# PowerSystem.net
KiCad netlist of a schematic drawn in Altium Designer
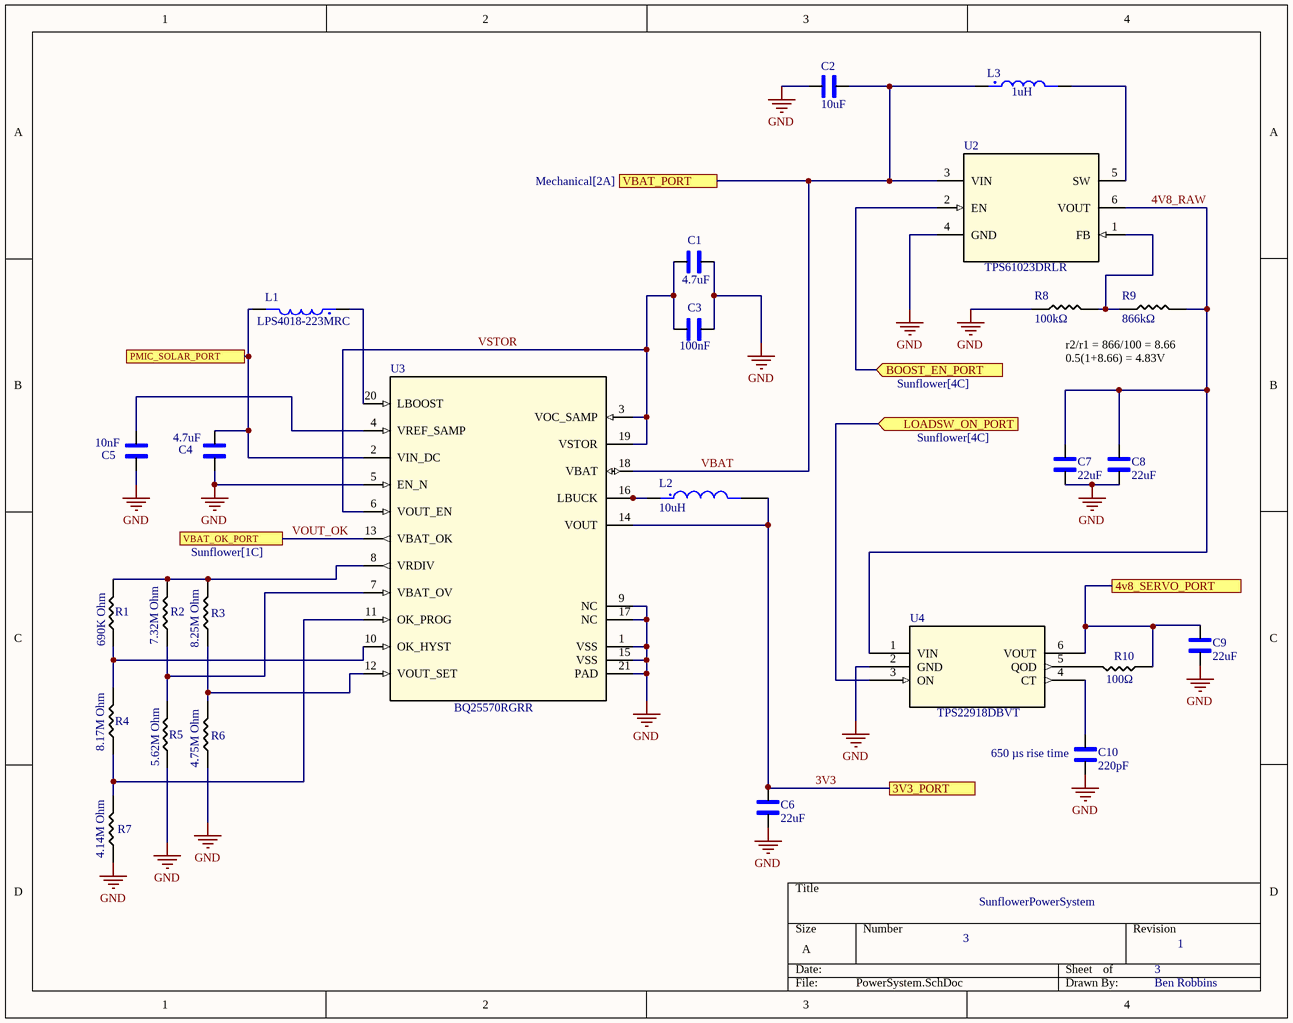
[diagram p0: PowerSystem.SchDoc]

(export (version "E")
  (design (tool "Eeschema 10.0.6"))
  (components
    (comp (ref "C1")
      (value "4.7uF")
      (footprint "0805_Capacitor")
      (description "4.7 µF ceramic input capacitor")
      (libsource (lib "SunflowerSCH") (part "C_0805_4u7"))
    )
    (comp (ref "C2")
      (value "10uF")
      (footprint "0805_Capacitor")
      (description "10 µF ceramic input capacitor")
      (libsource (lib "SunflowerSCH") (part "C_0805_10uF"))
    )
    (comp (ref "C3")
      (value "100nF")
      (footprint "0402_Capacitor")
      (description "0402 ceramic decoupling capacitor, 0.1 µF")
      (fields (field (name "MFR PART #") "CL05A105KA5NQNC") (field (name "LCSC PART#") "C52923"))
      (libsource (lib "SunflowerSCH") (part "C_0402_100nF"))
    )
    (comp (ref "C4")
      (value "4.7uF")
      (footprint "0805_Capacitor")
      (description "4.7 µF ceramic input capacitor")
      (libsource (lib "SunflowerSCH") (part "C_0805_4u7"))
    )
    (comp (ref "C5")
      (value "10nF")
      (footprint "0402_Capacitor")
      (description "10 nF low-leakage MPPT reference capacitor")
      (fields (field (name "MFR PART #") "CL05A105KA5NQNC") (field (name "LCSC PART#") "C52923"))
      (libsource (lib "SunflowerSCH") (part "C_0402_10nF"))
    )
    (comp (ref "C6")
      (value "22uF")
      (footprint "0805_Capacitor")
      (description "22 µF ceramic buck converter output capacitor")
      (libsource (lib "SunflowerSCH") (part "C_0805_22uF"))
    )
    (comp (ref "C7")
      (value "22uF")
      (footprint "0805_Capacitor")
      (description "22 µF ceramic buck converter output capacitor")
      (fields (field (name "DIGIKEY PART NUMBER") "1276-7092-1-ND"))
      (libsource (lib "SunflowerSCH") (part "C_0805_22uF"))
    )
    (comp (ref "C8")
      (value "22uF")
      (footprint "0805_Capacitor")
      (description "22 µF ceramic buck converter output capacitor")
      (fields (field (name "DIGIKEY PART NUMBER") "1276-7092-1-ND"))
      (libsource (lib "SunflowerSCH") (part "C_0805_22uF"))
    )
    (comp (ref "C9")
      (value "22uF")
      (footprint "0805_Capacitor")
      (description "22 µF ceramic buck converter output capacitor")
      (fields (field (name "DIGIKEY PART NUMBER") "1276-7092-1-ND"))
      (libsource (lib "SunflowerSCH") (part "C_0805_22uF"))
    )
    (comp (ref "C10")
      (value "220pF")
      (footprint "0603_Capacitor")
      (fields
        (field (name "MANUFACTURER") "KYOCERA AVX")
        (field (name "MANUFACTURER PART NUMBER") "KGM15ACG1E221JT")
        (field (name "TOLERANCE") "5%")
      )
      (libsource (lib "SunflowerSCH") (part "C_0603_220pF"))
    )
    (comp (ref "L1")
      (value "LPS4018-223MRC")
      (footprint "IND_LPS4018-223MRC")
      (description "22 ÂµH Shielded Drum Core Inductor 650 mA 360mOhm Max Nonstandard")
      (fields (field (name "MF") "Coilcraft"))
      (libsource (lib "SunflowerSCH") (part "LPS4018-223MRC"))
    )
    (comp (ref "L2")
      (value "10uH")
      (footprint "IND_LPS4018-223MRC")
      (description "10 µH buck converter inductor")
      (fields (field (name "MF") "Coilcraft") (field (name "MP") "LPS4018-223MRC"))
      (libsource (lib "SunflowerSCH") (part "L_10uH_Buck"))
    )
    (comp (ref "L3")
      (value "1uH")
      (footprint "WE-MAPI_4030")
      (fields
        (field (name "MANUFACTURER") "Wurth Elektronik")
        (field (name "MANUFACTURER PART NUMBER") "74438357010")
        (field (name "TOLERANCE") "20%")
      )
      (libsource (lib "SunflowerSCH") (part "L_1uH_Boost"))
    )
    (comp (ref "R1")
      (value "690K Ohm")
      (footprint "0603_Resistor")
      (description "690 kΩ, 1% tolerance, 0603 SMD battery-good hysteresis-setting resistor")
      (fields (field (name "Comment") "690K"))
      (libsource (lib "SunflowerSCH") (part "R_0603_690Kohm"))
    )
    (comp (ref "R2")
      (value "7.32M Ohm")
      (footprint "0603_Resistor")
      (description "7.32 MΩ: 4.75 MΩ, 1% tolerance, 0603 SMD buck converter output voltage-setting resistor")
      (fields (field (name "Comment") "7.32"))
      (libsource (lib "SunflowerSCH") (part "R_0603_7.32MOhm"))
    )
    (comp (ref "R3")
      (value "8.25M Ohm")
      (footprint "0603_Resistor")
      (description "8.25 MΩ, 1% tolerance, 0603 SMD buck converter output voltage-setting resistor")
      (fields (field (name "Comment") "8.25M"))
      (libsource (lib "SunflowerSCH") (part "R_0603_8.25MOhm"))
    )
    (comp (ref "R4")
      (value "8.17M Ohm")
      (footprint "0603_Resistor")
      (description "8.17 MΩ, 1% tolerance, 0603 SMD battery-good hysteresis-setting resistor")
      (fields (field (name "Comment") "8.17M"))
      (libsource (lib "SunflowerSCH") (part "R_0603_8.17Mohm"))
    )
    (comp (ref "R5")
      (value "5.62M Ohm")
      (footprint "0603_Resistor")
      (description "5.62 MΩ: 4.75 MΩ, 1% tolerance, 0603 SMD buck converter output voltage-setting resistor")
      (fields (field (name "Comment") "5.62"))
      (libsource (lib "SunflowerSCH") (part "R_0603_5.62MOhm"))
    )
    (comp (ref "R6")
      (value "4.75M Ohm")
      (footprint "0603_Resistor")
      (description "4.75 MΩ, 1% tolerance, 0603 SMD buck converter output voltage-setting resistor")
      (fields (field (name "Comment") "4.75M"))
      (libsource (lib "SunflowerSCH") (part "R_0603_4.75MOhm_1"))
    )
    (comp (ref "R7")
      (value "4.14M Ohm")
      (footprint "0603_Resistor")
      (description "4.14 MΩ, 1% tolerance, 0603 SMD battery-good hysteresis-setting resistor")
      (fields (field (name "Comment") "4.14M"))
      (libsource (lib "SunflowerSCH") (part "R_0603_4.14Mohm"))
    )
    (comp (ref "R8")
      (value "100kΩ")
      (footprint "0603_Resistor")
      (description "Res Thick Film 0603 100K Ohm 1% 0.1W(1/10W) ±100ppm/C Pad SMD Automotive T/R")
      (fields
        (field (name "MANUFACTURER") "Stackpole Electronics")
        (field (name "MANUFACTURER PART NUMBER") "RMCF0603FT100K")
      )
      (libsource (lib "SunflowerSCH") (part "R_0603_100kOhm"))
    )
    (comp (ref "R9")
      (value "866kΩ")
      (footprint "0603_Resistor")
      (description "Res Thick Film 0603 866K Ohm 1% 0.1W(1/10W) ±100ppm/C Pad SMD Automotive T/R")
      (fields
        (field (name "MANUFACTURER") "Panasonic")
        (field (name "MANUFACTURER PART NUMBER") "ERJ-3EKF8663V")
      )
      (libsource (lib "SunflowerSCH") (part "R_0603_866kOhm"))
    )
    (comp (ref "R10")
      (value "100Ω")
      (footprint "0603_Resistor")
      (description "Res Thick Film 0603 100 Ohm 1% 0.1W(1/10W) ±100ppm/C Pad SMD Automotive T/R")
      (fields
        (field (name "MANUFACTURER") "Panasonic")
        (field (name "MANUFACTURER PART NUMBER") "ERJ3EKF1000V")
      )
      (libsource (lib "SunflowerSCH") (part "R_0603_100Ohm"))
    )
    (comp (ref "U2")
      (value "TPS61023DRLR")
      (footprint "DRL0006A")
      (description "3.7-A boost converter with 0.5-V ultra-low input voltage 6-SOT-5X3 -40 to 125")
      (fields
        (field (name "DIGIKEY PART NUMBER") "296-TPS61023DRLRCT-ND")
        (field (name "COPYRIGHT") "Copyright (C) 2025 Ultra Librarian. All rights reserved.")
      )
      (libsource (lib "SunflowerSCH") (part "TPS61023DRLR"))
    )
    (comp (ref "U3")
      (value "BQ25570RGRR")
      (footprint "RGR0020A")
      (fields
        (field (name "ALTERNATE_PARTNUMBER") "BQ25570RGRT")
        (field (name "MANUFACTURER") "Texas Instruments")
        (field (name "DIGIKEY PART NUMBER") "296-39934-1-ND")
        (field (name "COPYRIGHT") "Copyright (C) 2026 Ultra Librarian. All rights reserved.")
      )
      (libsource (lib "SunflowerSCH") (part "BQ25570RGRR"))
    )
    (comp (ref "U4")
      (value "TPS22918DBVT")
      (footprint "TPS22918DBVT")
      (description "2A Load Switch")
      (libsource (lib "SunflowerSCH") (part "TPS22918DBVT"))
    )
  )
  (nets
    (net (code "1") (name "/3V3") (class "Default")
      (node (ref "C6") (pin "2") (pinfunction "2_2") (pintype "passive"))
      (node (ref "L2") (pin "2") (pinfunction "2_2") (pintype "passive"))
      (node (ref "U3") (pin "14") (pinfunction "VOUT_14") (pintype "power_in"))
    )
    (net (code "2") (name "/4V8_RAW") (class "Default")
      (node (ref "C7") (pin "2") (pinfunction "2_2") (pintype "passive"))
      (node (ref "C8") (pin "2") (pinfunction "2_2") (pintype "passive"))
      (node (ref "R9") (pin "2") (pinfunction "2_2") (pintype "passive"))
      (node (ref "U2") (pin "6") (pinfunction "VOUT_6") (pintype "power_in"))
      (node (ref "U4") (pin "1") (pinfunction "VIN_1") (pintype "power_in"))
    )
    (net (code "3") (name "/4v8_SERVO_PORT") (class "Default")
      (node (ref "C9") (pin "2") (pinfunction "2_2") (pintype "passive"))
      (node (ref "R10") (pin "1") (pinfunction "1_1") (pintype "passive"))
      (node (ref "U4") (pin "6") (pinfunction "VOUT_6") (pintype "power_in"))
    )
    (net (code "4") (name "/BOOST_EN_PORT") (class "Default")
      (node (ref "U2") (pin "2") (pinfunction "EN_2") (pintype "input"))
    )
    (net (code "5") (name "/LOADSW_ON_PORT") (class "Default")
      (node (ref "U4") (pin "3") (pinfunction "ON_3") (pintype "input"))
    )
    (net (code "6") (name "/PMIC_SOLAR_PORT") (class "Default")
      (node (ref "C4") (pin "2") (pinfunction "2_2") (pintype "passive"))
      (node (ref "L1") (pin "2") (pinfunction "2_2") (pintype "passive"))
      (node (ref "U3") (pin "2") (pinfunction "VIN_DC_2") (pintype "power_in"))
    )
    (net (code "7") (name "/VBAT") (class "Default")
      (node (ref "C2") (pin "2") (pinfunction "2_2") (pintype "passive"))
      (node (ref "L3") (pin "1") (pinfunction "1_1") (pintype "passive"))
      (node (ref "U2") (pin "3") (pinfunction "VIN_3") (pintype "power_in"))
      (node (ref "U3") (pin "18") (pinfunction "VBAT_18") (pintype "bidirectional"))
    )
    (net (code "8") (name "/VOUT_OK") (class "Default")
      (node (ref "U3") (pin "13") (pinfunction "VBAT_OK_13") (pintype "output"))
    )
    (net (code "9") (name "/VSTOR") (class "Default")
      (node (ref "C1") (pin "1") (pinfunction "1_1") (pintype "passive"))
      (node (ref "C3") (pin "1") (pinfunction "1_1") (pintype "passive"))
      (node (ref "U3") (pin "19") (pinfunction "VSTOR_19") (pintype "power_in"))
      (node (ref "U3") (pin "3") (pinfunction "VOC_SAMP_3") (pintype "input"))
      (node (ref "U3") (pin "6") (pinfunction "VOUT_EN_6") (pintype "input"))
    )
    (net (code "10") (name "GND") (class "Default")
      (node (ref "C1") (pin "2") (pinfunction "2_2") (pintype "passive"))
      (node (ref "C10") (pin "1") (pinfunction "1_1") (pintype "passive"))
      (node (ref "C2") (pin "1") (pinfunction "1_1") (pintype "passive"))
      (node (ref "C3") (pin "2") (pinfunction "2_2") (pintype "passive"))
      (node (ref "C4") (pin "1") (pinfunction "1_1") (pintype "passive"))
      (node (ref "C5") (pin "1") (pinfunction "1_1") (pintype "passive"))
      (node (ref "C6") (pin "1") (pinfunction "1_1") (pintype "passive"))
      (node (ref "C7") (pin "1") (pinfunction "1_1") (pintype "passive"))
      (node (ref "C8") (pin "1") (pinfunction "1_1") (pintype "passive"))
      (node (ref "C9") (pin "1") (pinfunction "1_1") (pintype "passive"))
      (node (ref "R5") (pin "1") (pinfunction "1_1") (pintype "passive"))
      (node (ref "R6") (pin "1") (pinfunction "1_1") (pintype "passive"))
      (node (ref "R7") (pin "1") (pinfunction "1_1") (pintype "passive"))
      (node (ref "R8") (pin "1") (pinfunction "1_1") (pintype "passive"))
      (node (ref "U2") (pin "4") (pinfunction "GND_4") (pintype "power_in"))
      (node (ref "U3") (pin "1") (pinfunction "VSS_1") (pintype "power_in"))
      (node (ref "U3") (pin "15") (pinfunction "VSS_15") (pintype "power_in"))
      (node (ref "U3") (pin "17") (pinfunction "NC_17") (pintype "passive"))
      (node (ref "U3") (pin "21") (pinfunction "PAD_21") (pintype "power_in"))
      (node (ref "U3") (pin "5") (pinfunction "EN_N_5") (pintype "input"))
      (node (ref "U3") (pin "9") (pinfunction "NC_9") (pintype "power_in"))
      (node (ref "U4") (pin "2") (pinfunction "GND_2") (pintype "power_in"))
    )
    (net (code "11") (name "Net-(U2-FB)") (class "Default")
      (node (ref "R8") (pin "2") (pinfunction "2_2") (pintype "passive"))
      (node (ref "R9") (pin "1") (pinfunction "1_1") (pintype "passive"))
      (node (ref "U2") (pin "1") (pinfunction "FB_1") (pintype "input"))
    )
    (net (code "12") (name "Net-(U2-SW)") (class "Default")
      (node (ref "L3") (pin "2") (pinfunction "2_2") (pintype "passive"))
      (node (ref "U2") (pin "5") (pinfunction "SW_5") (pintype "power_in"))
    )
    (net (code "13") (name "Net-(U3-LBOOST)") (class "Default")
      (node (ref "L1") (pin "1") (pinfunction "1_1") (pintype "passive"))
      (node (ref "U3") (pin "20") (pinfunction "LBOOST_20") (pintype "input"))
    )
    (net (code "14") (name "Net-(U3-LBUCK)") (class "Default")
      (node (ref "L2") (pin "1") (pinfunction "1_1") (pintype "passive"))
      (node (ref "U3") (pin "16") (pinfunction "LBUCK_16") (pintype "passive"))
    )
    (net (code "15") (name "Net-(U3-OK_HYST)") (class "Default")
      (node (ref "R1") (pin "1") (pinfunction "1_1") (pintype "passive"))
      (node (ref "R4") (pin "2") (pinfunction "2_2") (pintype "passive"))
      (node (ref "U3") (pin "10") (pinfunction "OK_HYST_10") (pintype "input"))
    )
    (net (code "16") (name "Net-(U3-OK_PROG)") (class "Default")
      (node (ref "R4") (pin "1") (pinfunction "1_1") (pintype "passive"))
      (node (ref "R7") (pin "2") (pinfunction "2_2") (pintype "passive"))
      (node (ref "U3") (pin "11") (pinfunction "OK_PROG_11") (pintype "input"))
    )
    (net (code "17") (name "Net-(U3-VBAT_OV)") (class "Default")
      (node (ref "R2") (pin "1") (pinfunction "1_1") (pintype "passive"))
      (node (ref "R5") (pin "2") (pinfunction "2_2") (pintype "passive"))
      (node (ref "U3") (pin "7") (pinfunction "VBAT_OV_7") (pintype "input"))
    )
    (net (code "18") (name "Net-(U3-VOUT_SET)") (class "Default")
      (node (ref "R3") (pin "1") (pinfunction "1_1") (pintype "passive"))
      (node (ref "R6") (pin "2") (pinfunction "2_2") (pintype "passive"))
      (node (ref "U3") (pin "12") (pinfunction "VOUT_SET_12") (pintype "input"))
    )
    (net (code "19") (name "Net-(U3-VRDIV)") (class "Default")
      (node (ref "R1") (pin "2") (pinfunction "2_2") (pintype "passive"))
      (node (ref "R2") (pin "2") (pinfunction "2_2") (pintype "passive"))
      (node (ref "R3") (pin "2") (pinfunction "2_2") (pintype "passive"))
      (node (ref "U3") (pin "8") (pinfunction "VRDIV_8") (pintype "output"))
    )
    (net (code "20") (name "Net-(U3-VREF_SAMP)") (class "Default")
      (node (ref "C5") (pin "2") (pinfunction "2_2") (pintype "passive"))
      (node (ref "U3") (pin "4") (pinfunction "VREF_SAMP_4") (pintype "input"))
    )
    (net (code "21") (name "Net-(U4-CT)") (class "Default")
      (node (ref "C10") (pin "2") (pinfunction "2_2") (pintype "passive"))
      (node (ref "U4") (pin "4") (pinfunction "CT_4") (pintype "output"))
    )
    (net (code "22") (name "Net-(U4-QOD)") (class "Default")
      (node (ref "R10") (pin "2") (pinfunction "2_2") (pintype "passive"))
      (node (ref "U4") (pin "5") (pinfunction "QOD_5") (pintype "output"))
    )
  )
)
